# SPI.net
KiCad netlist of a schematic drawn in Altium Designer
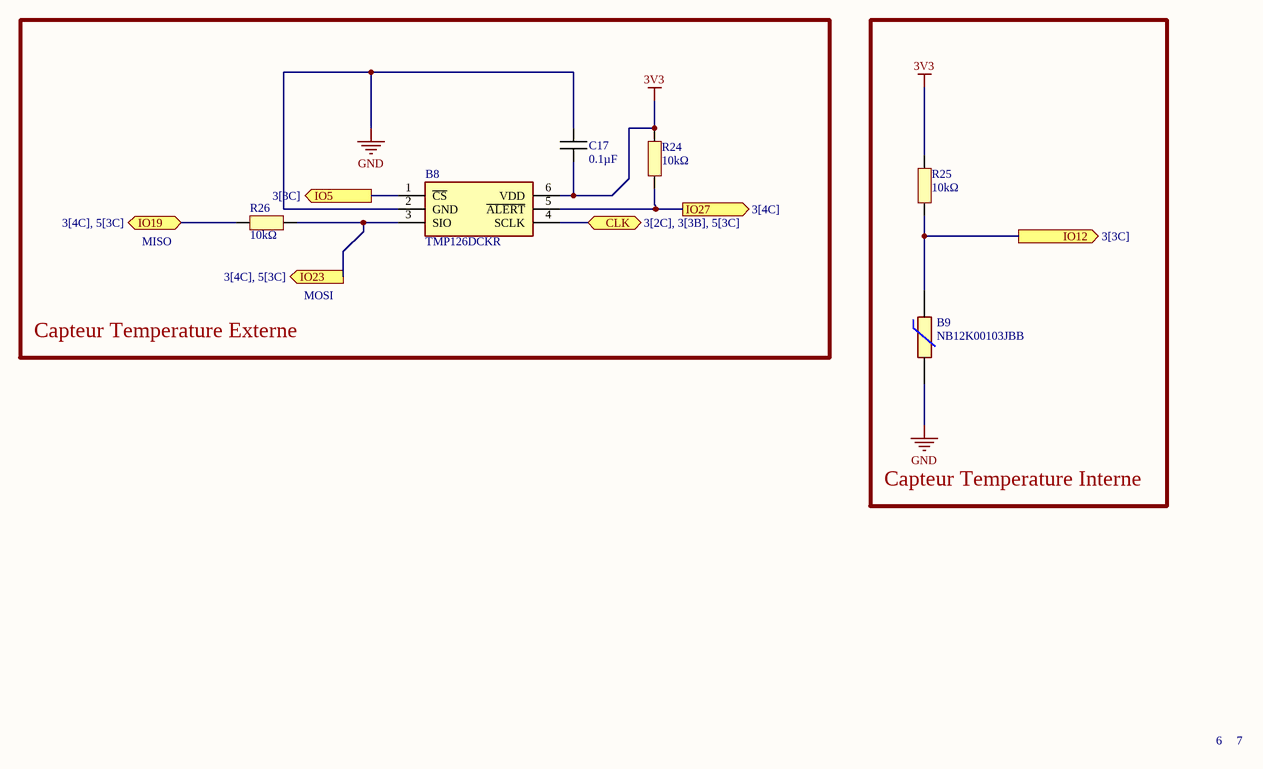
[diagram p0: SPI.SchDoc]

(export (version "E")
  (design (tool "Eeschema 10.0.6"))
  (components
    (comp (ref "B8")
      (value "TMP126DCKR")
      (footprint "SOT65P210X110-6N")
      (fields (field (name "MOUSER PART NUMBER") "595-TMP126DCKR"))
      (libsource (lib "SCHLibrary") (part "TMP126DCKR"))
    )
    (comp (ref "B9")
      (value "NB12K00103JBB")
      (footprint "RESC2212X50N")
      (description "NTC SMD Thermistor, NB12K, 10K, 5% AVX 10k 0805 Protection NTC Thermistor, 5s, 2 x 1.25 x 1.3mm")
      (fields (field (name "MOUSER PART NUMBER") "581-NB12K00103JBB"))
      (libsource (lib "SCHLibrary") (part "NB12K00103JBB"))
    )
    (comp (ref "C17")
      (value "0.1µF")
      (footprint "CAPC1005X06N")
      (libsource (lib "SCHLibrary") (part "Capacitor"))
    )
    (comp (ref "R24") (value "10kΩ") (footprint "RESC1005X06N") (libsource (lib "") (part "Resistor_2")))
    (comp (ref "R25")
      (value "10kΩ")
      (footprint "RESC1005X06N")
      (libsource (lib "SCHLibrary") (part "Resistor"))
    )
    (comp (ref "R26") (value "10kΩ") (footprint "RESC1005X06N") (libsource (lib "") (part "Resistor_1")))
  )
  (nets
    (net (code "1") (name "/CLK") (class "Default")
      (node (ref "B8") (pin "4") (pinfunction "SCLK_4") (pintype "passive"))
    )
    (net (code "2") (name "/IO5") (class "Default")
      (node (ref "B8") (pin "1") (pinfunction "~{CS}_1") (pintype "passive"))
    )
    (net (code "3") (name "/IO12") (class "Default")
      (node (ref "B9") (pin "1") (pinfunction "1_1") (pintype "passive"))
      (node (ref "R25") (pin "2") (pinfunction "2_2") (pintype "passive"))
    )
    (net (code "4") (name "/IO19") (class "Default")
      (node (ref "R26") (pin "2") (pinfunction "2_2") (pintype "passive"))
    )
    (net (code "5") (name "/IO23") (class "Default")
      (node (ref "B8") (pin "3") (pinfunction "SIO_3") (pintype "passive"))
      (node (ref "R26") (pin "1") (pinfunction "1_1") (pintype "passive"))
    )
    (net (code "6") (name "/IO27") (class "Default")
      (node (ref "B8") (pin "5") (pinfunction "~{ALERT}_5") (pintype "passive"))
      (node (ref "R24") (pin "1") (pinfunction "1_1") (pintype "passive"))
    )
    (net (code "7") (name "3V3") (class "Default")
      (node (ref "B8") (pin "6") (pinfunction "VDD_6") (pintype "passive"))
      (node (ref "C17") (pin "1") (pinfunction "1_1") (pintype "passive"))
      (node (ref "R24") (pin "2") (pinfunction "2_2") (pintype "passive"))
      (node (ref "R25") (pin "1") (pinfunction "1_1") (pintype "passive"))
    )
    (net (code "8") (name "GND") (class "Default")
      (node (ref "B8") (pin "2") (pinfunction "GND_2") (pintype "passive"))
      (node (ref "B9") (pin "2") (pinfunction "2_2") (pintype "passive"))
      (node (ref "C17") (pin "2") (pinfunction "2_2") (pintype "passive"))
    )
  )
)
